# Sensor_v1_0.net
KiCad netlist of a schematic drawn in EAGLE
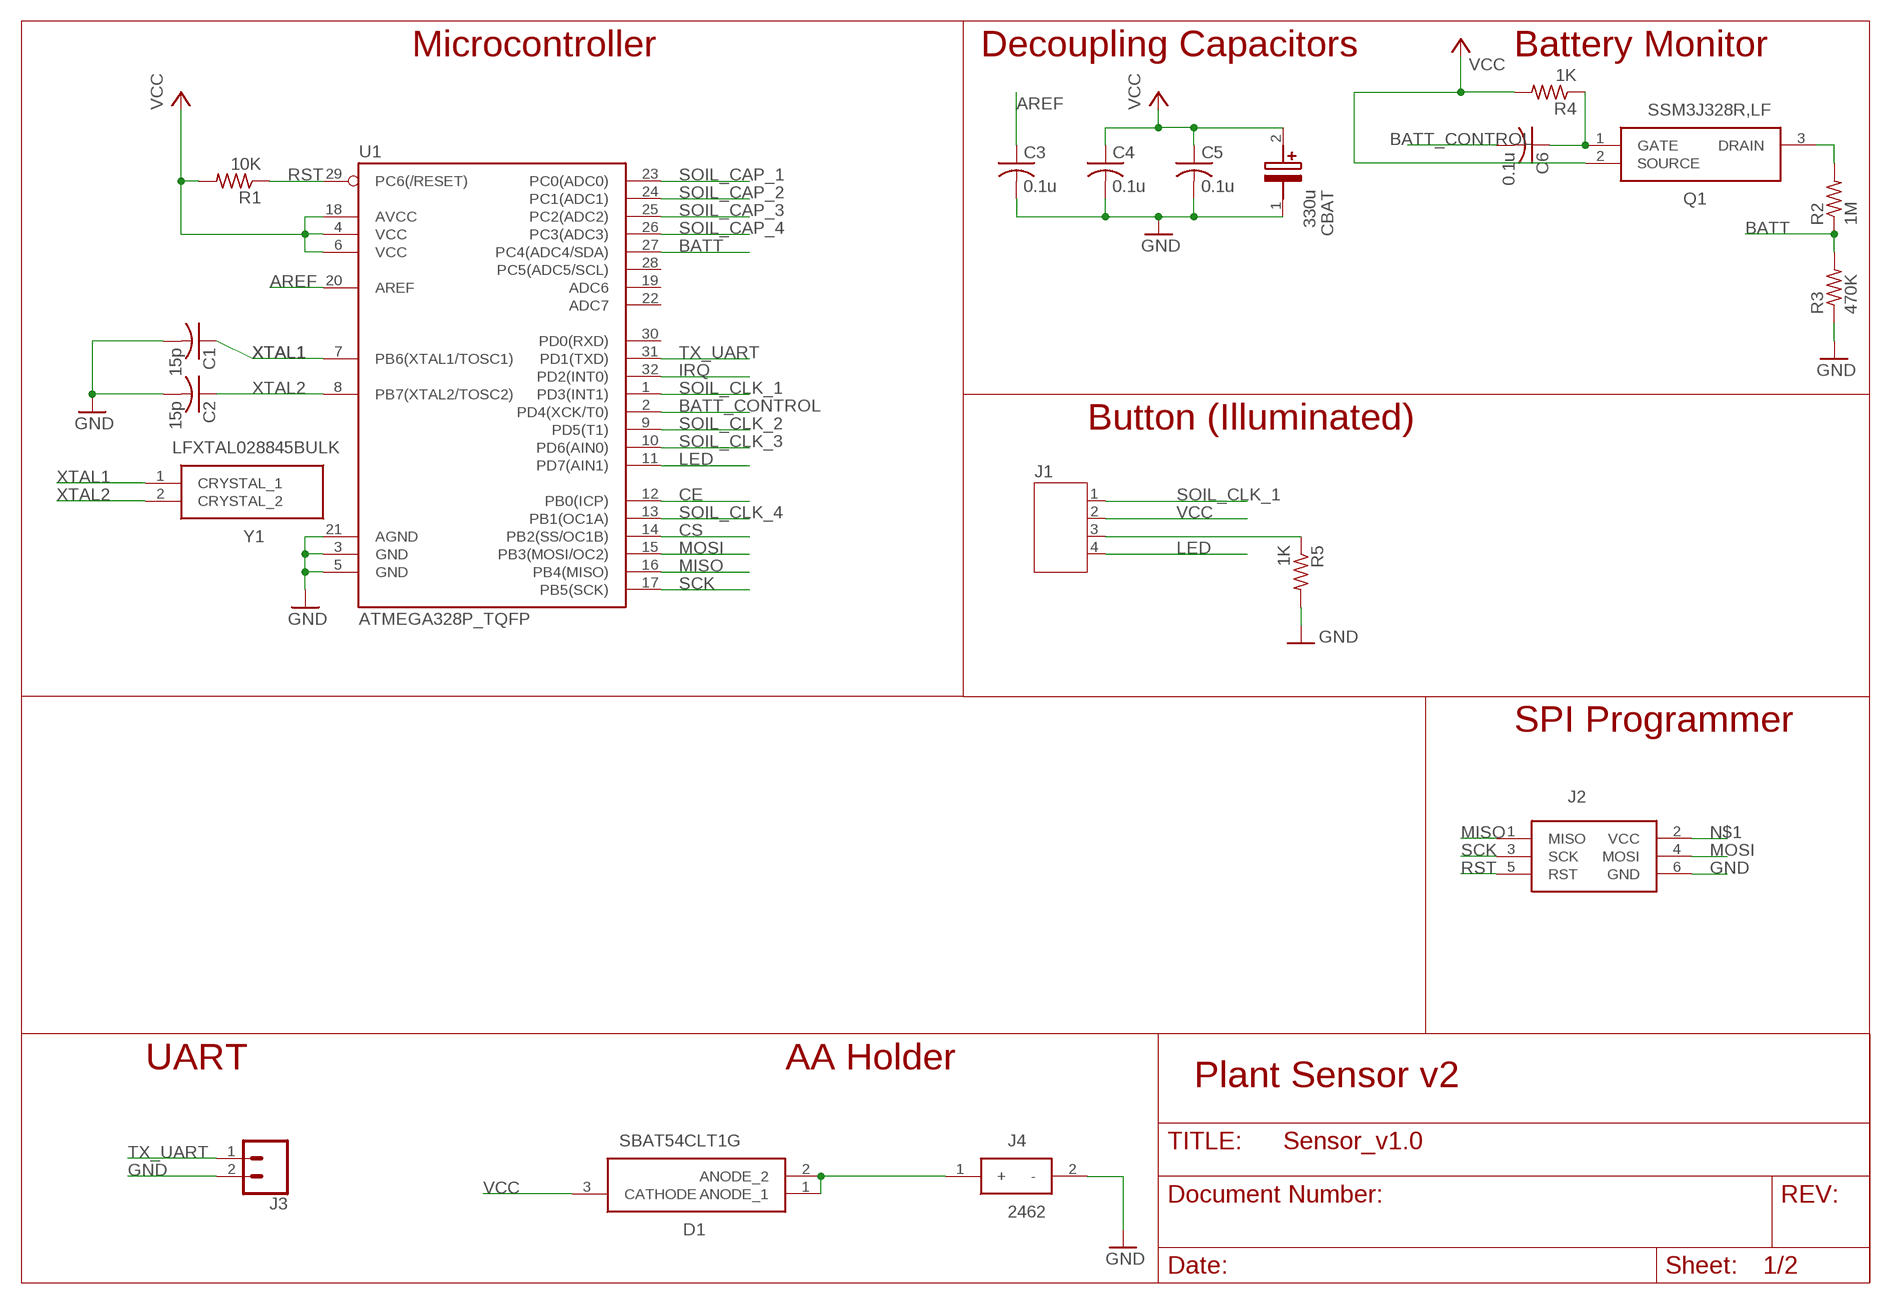
[diagram p0: schematic, sheet 1]
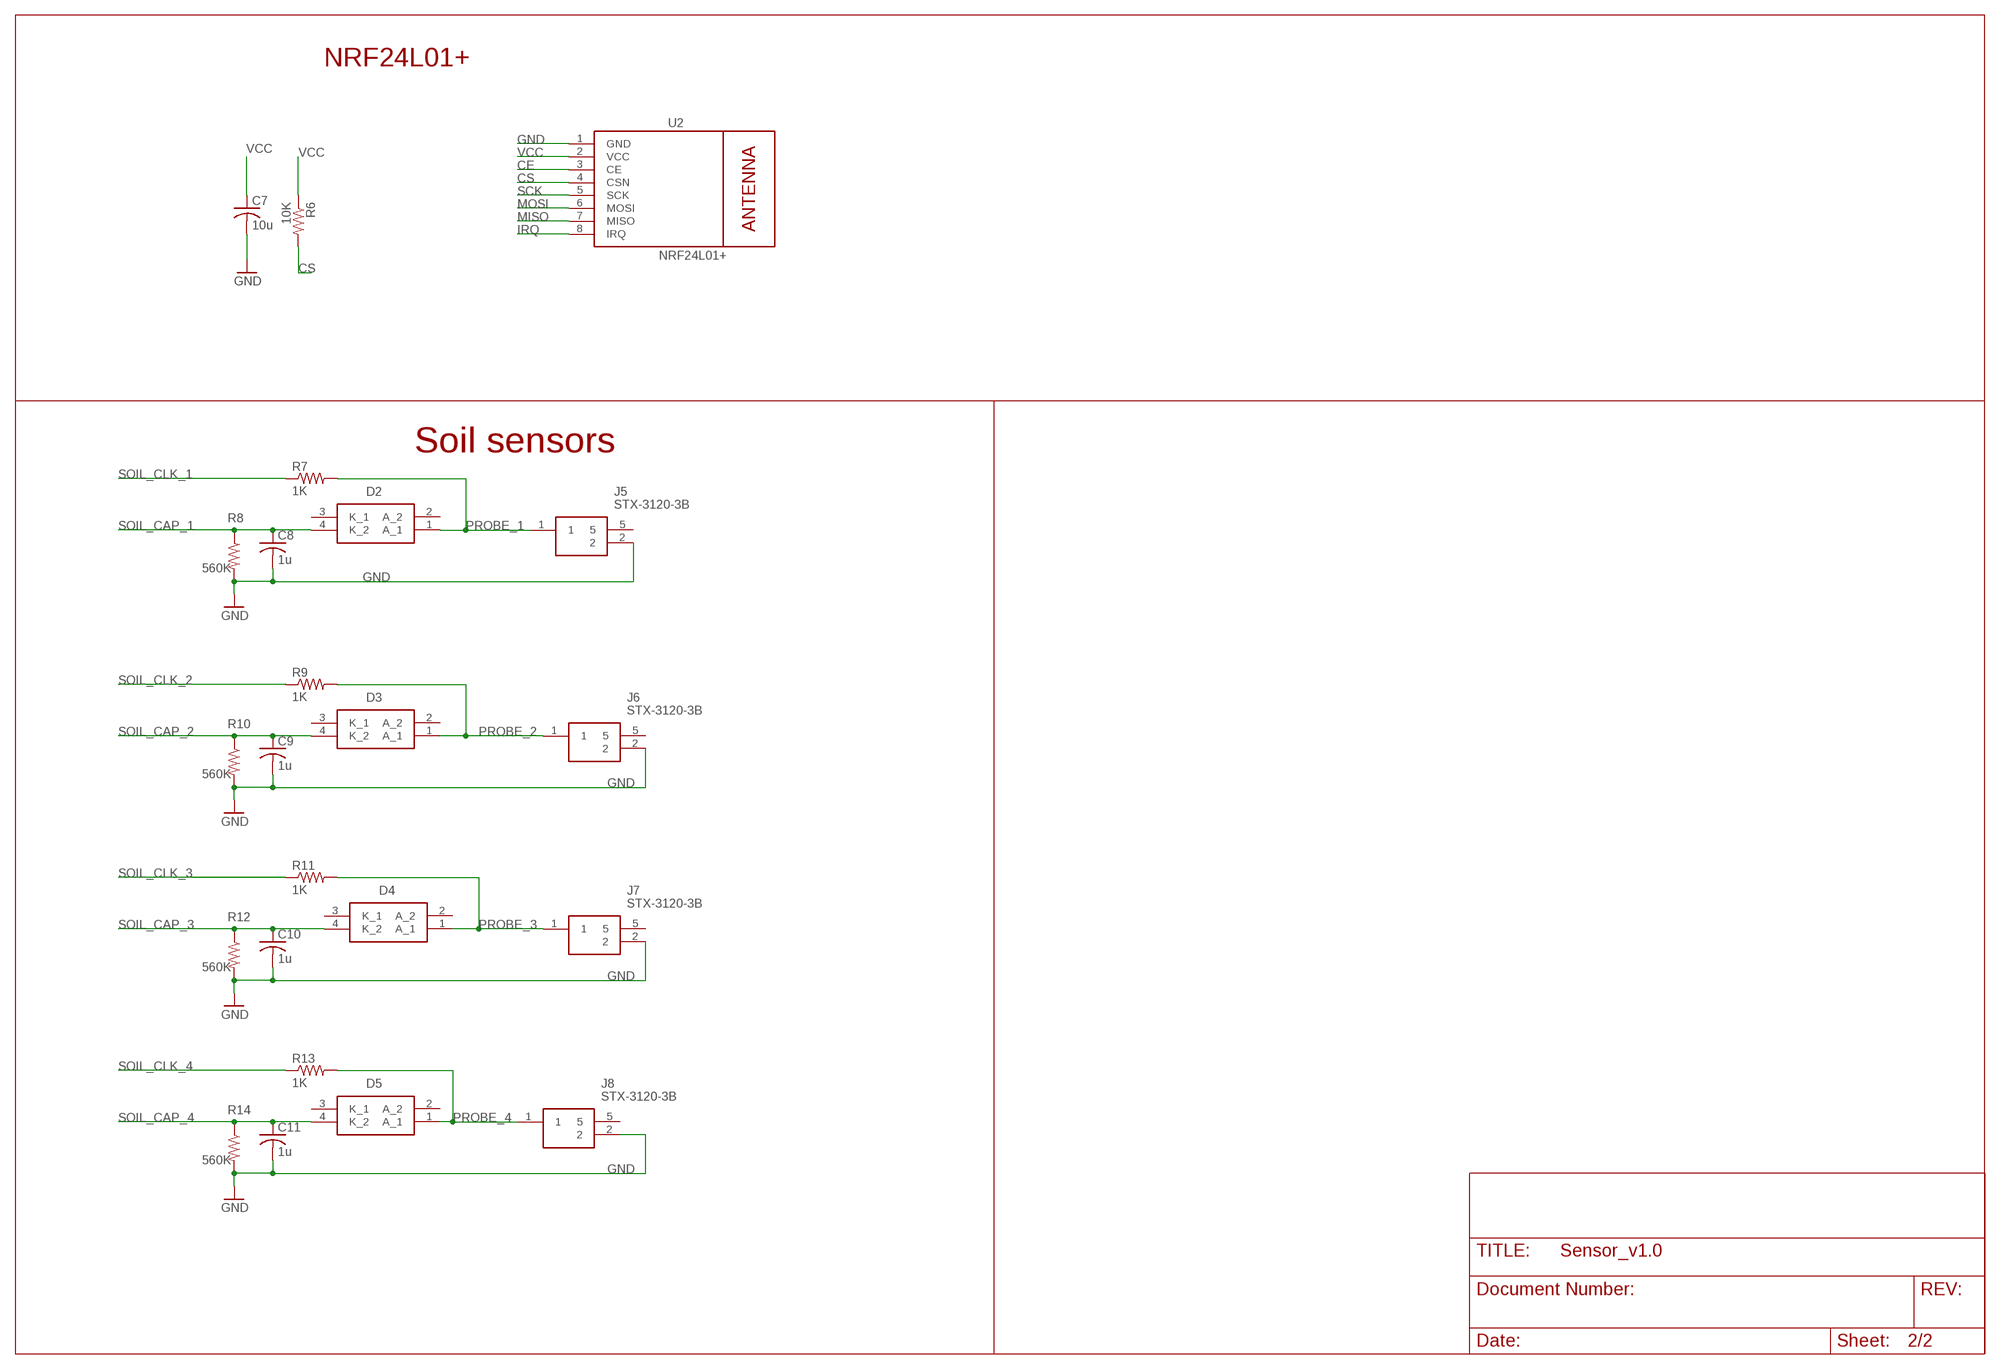
[diagram p1: schematic, sheet 2]

(export (version "E")
  (design (tool "Eeschema 10.0.6"))
  (components
    (comp (ref "C7")
      (value "10u")
      (footprint "eagle-import:SMD-0805")
      (libsource (lib "eagle-import") (part "CAPACITOR-SMD-0805"))
    )
    (comp (ref "C8")
      (value "1u")
      (footprint "eagle-import:SMD-0805")
      (libsource (lib "eagle-import") (part "CAPACITOR-SMD-0805"))
    )
    (comp (ref "C9")
      (value "1u")
      (footprint "eagle-import:SMD-0805")
      (libsource (lib "eagle-import") (part "CAPACITOR-SMD-0805"))
    )
    (comp (ref "C10")
      (value "1u")
      (footprint "eagle-import:SMD-0805")
      (libsource (lib "eagle-import") (part "CAPACITOR-SMD-0805"))
    )
    (comp (ref "C11")
      (value "1u")
      (footprint "eagle-import:SMD-0805")
      (libsource (lib "eagle-import") (part "CAPACITOR-SMD-0805"))
    )
    (comp (ref "D2")
      (value "1SS384TE85LF")
      (footprint "eagle-import:SOP65P210X110-4N")
      (fields (field (name "MOUSER_PART_NUMBER") "757-1SS384TE85LF"))
      (libsource (lib "eagle-import") (part "1SS384TE85LF"))
    )
    (comp (ref "D3")
      (value "1SS384TE85LF")
      (footprint "eagle-import:SOP65P210X110-4N")
      (fields (field (name "MOUSER_PART_NUMBER") "757-1SS384TE85LF"))
      (libsource (lib "eagle-import") (part "1SS384TE85LF"))
    )
    (comp (ref "D4")
      (value "1SS384TE85LF")
      (footprint "eagle-import:SOP65P210X110-4N")
      (fields (field (name "MOUSER_PART_NUMBER") "757-1SS384TE85LF"))
      (libsource (lib "eagle-import") (part "1SS384TE85LF"))
    )
    (comp (ref "D5")
      (value "1SS384TE85LF")
      (footprint "eagle-import:SOP65P210X110-4N")
      (fields (field (name "MOUSER_PART_NUMBER") "757-1SS384TE85LF"))
      (libsource (lib "eagle-import") (part "1SS384TE85LF"))
    )
    (comp (ref "J5")
      (value "STX-3120-3B")
      (footprint "eagle-import:STX31203B")
      (fields (field (name "MOUSER_PART_NUMBER") "806-STX-3120-3B"))
      (libsource (lib "eagle-import") (part "STX-3120-3B"))
    )
    (comp (ref "J6")
      (value "STX-3120-3B")
      (footprint "eagle-import:STX31203B")
      (fields (field (name "MOUSER_PART_NUMBER") "806-STX-3120-3B"))
      (libsource (lib "eagle-import") (part "STX-3120-3B"))
    )
    (comp (ref "J7")
      (value "STX-3120-3B")
      (footprint "eagle-import:STX31203B")
      (fields (field (name "MOUSER_PART_NUMBER") "806-STX-3120-3B"))
      (libsource (lib "eagle-import") (part "STX-3120-3B"))
    )
    (comp (ref "J8")
      (value "STX-3120-3B")
      (footprint "eagle-import:STX31203B")
      (fields (field (name "MOUSER_PART_NUMBER") "806-STX-3120-3B"))
      (libsource (lib "eagle-import") (part "STX-3120-3B"))
    )
    (comp (ref "R6")
      (value "10K")
      (footprint "eagle-import:SMD-0805")
      (libsource (lib "eagle-import") (part "RESISTOR-SMD-0805"))
    )
    (comp (ref "R7")
      (value "1K")
      (footprint "eagle-import:SMD-0805")
      (libsource (lib "eagle-import") (part "RESISTOR-SMD-0805"))
    )
    (comp (ref "R8")
      (value "560K")
      (footprint "eagle-import:SMD-0805")
      (libsource (lib "eagle-import") (part "RESISTOR-SMD-0805"))
    )
    (comp (ref "R9")
      (value "1K")
      (footprint "eagle-import:SMD-0805")
      (libsource (lib "eagle-import") (part "RESISTOR-SMD-0805"))
    )
    (comp (ref "R10")
      (value "560K")
      (footprint "eagle-import:SMD-0805")
      (libsource (lib "eagle-import") (part "RESISTOR-SMD-0805"))
    )
    (comp (ref "R11")
      (value "1K")
      (footprint "eagle-import:SMD-0805")
      (libsource (lib "eagle-import") (part "RESISTOR-SMD-0805"))
    )
    (comp (ref "R12")
      (value "560K")
      (footprint "eagle-import:SMD-0805")
      (libsource (lib "eagle-import") (part "RESISTOR-SMD-0805"))
    )
    (comp (ref "R13")
      (value "1K")
      (footprint "eagle-import:SMD-0805")
      (libsource (lib "eagle-import") (part "RESISTOR-SMD-0805"))
    )
    (comp (ref "R14")
      (value "560K")
      (footprint "eagle-import:SMD-0805")
      (libsource (lib "eagle-import") (part "RESISTOR-SMD-0805"))
    )
    (comp (ref "U2")
      (value "NRF24L01+")
      (footprint "eagle-import:WIRELESS-NRF24L01")
      (libsource (lib "eagle-import") (part "WIRELESS-NRF24L01"))
    )
    (comp (ref "C1")
      (value "15p")
      (footprint "eagle-import:SMD-0805")
      (libsource (lib "eagle-import") (part "CAPACITOR-SMD-0805"))
    )
    (comp (ref "C2")
      (value "15p")
      (footprint "eagle-import:SMD-0805")
      (libsource (lib "eagle-import") (part "CAPACITOR-SMD-0805"))
    )
    (comp (ref "C3")
      (value "0.1u")
      (footprint "eagle-import:SMD-0805")
      (libsource (lib "eagle-import") (part "CAPACITOR-SMD-0805"))
    )
    (comp (ref "C4")
      (value "0.1u")
      (footprint "eagle-import:SMD-0805")
      (libsource (lib "eagle-import") (part "CAPACITOR-SMD-0805"))
    )
    (comp (ref "C5")
      (value "0.1u")
      (footprint "eagle-import:SMD-0805")
      (libsource (lib "eagle-import") (part "CAPACITOR-SMD-0805"))
    )
    (comp (ref "C6")
      (value "0.1u")
      (footprint "eagle-import:SMD-0805")
      (libsource (lib "eagle-import") (part "CAPACITOR-SMD-0805"))
    )
    (comp (ref "CBAT")
      (value "330u")
      (footprint "eagle-import:SMD_LYTIC_D8")
      (fields
        (field (name "MANUFACTURER_PART_NUMBER") "EEE-FNC271XUP")
        (field (name "MOUSER_PART_NUMBER") "667-EEE-FNC271XUP")
      )
      (libsource (lib "eagle-import") (part "EEE-FNC271XUP"))
    )
    (comp (ref "D1")
      (value "SBAT54CLT1G")
      (footprint "eagle-import:SOT96P237X111-3N")
      (fields (field (name "MOUSER_PART_NUMBER") "863-SBAT54CLT1G"))
      (libsource (lib "eagle-import") (part "SBAT54CLT1G"))
    )
    (comp (ref "J1")
      (value "JST-PH4")
      (footprint "eagle-import:JST-PH4")
      (libsource (lib "eagle-import") (part "JST-PH4"))
    )
    (comp (ref "J2")
      (value "ISP")
      (footprint "eagle-import:AVRISP")
      (libsource (lib "eagle-import") (part "AVRISP-6"))
    )
    (comp (ref "J3")
      (value "CONN_02")
      (footprint "eagle-import:1X02")
      (libsource (lib "eagle-import") (part "CONN_02"))
    )
    (comp (ref "J4")
      (value "2462")
      (footprint "eagle-import:2462")
      (fields (field (name "MOUSER_PART_NUMBER") "534-2462"))
      (libsource (lib "eagle-import") (part "2462"))
    )
    (comp (ref "Q1")
      (value "SSM3J328R,LF")
      (footprint "eagle-import:SOTFL95P240X88-3N")
      (fields (field (name "MOUSER_PART_NUMBER") "757-SSM3J328RLF"))
      (libsource (lib "eagle-import") (part "SSM3J328R,LF"))
    )
    (comp (ref "R1")
      (value "10K")
      (footprint "eagle-import:SMD-0805")
      (libsource (lib "eagle-import") (part "RESISTOR-SMD-0805"))
    )
    (comp (ref "R2")
      (value "1M")
      (footprint "eagle-import:SMD-0805")
      (libsource (lib "eagle-import") (part "RESISTOR-SMD-0805"))
    )
    (comp (ref "R3")
      (value "470K")
      (footprint "eagle-import:SMD-0805")
      (libsource (lib "eagle-import") (part "RESISTOR-SMD-0805"))
    )
    (comp (ref "R4")
      (value "1K")
      (footprint "eagle-import:SMD-0805")
      (libsource (lib "eagle-import") (part "RESISTOR-SMD-0805"))
    )
    (comp (ref "R5")
      (value "1K")
      (footprint "eagle-import:SMD-0805")
      (libsource (lib "eagle-import") (part "RESISTOR-SMD-0805"))
    )
    (comp (ref "U1")
      (value "ATMEGA328P_TQFP")
      (footprint "eagle-import:TQFP32-08")
      (libsource (lib "eagle-import") (part "ATMEGA328P_TQFP"))
    )
    (comp (ref "Y1")
      (value "LFXTAL028845BULK")
      (footprint "eagle-import:LFXTAL028845BULK")
      (libsource (lib "eagle-import") (part "LFXTAL028845BULK"))
    )
  )
  (nets
    (net (code "1") (name "AREF") (class "Default")
      (node (ref "C3") (pin "1") (pinfunction "1_1") (pintype "passive"))
      (node (ref "U1") (pin "20") (pinfunction "AREF_20") (pintype "bidirectional"))
    )
    (net (code "2") (name "BATT") (class "Default")
      (node (ref "R2") (pin "1") (pinfunction "1_1") (pintype "passive"))
      (node (ref "R3") (pin "2") (pinfunction "2_2") (pintype "passive"))
      (node (ref "U1") (pin "27") (pinfunction "PC4(ADC4/SDA)_27") (pintype "bidirectional"))
    )
    (net (code "3") (name "BATT_CONTROL") (class "Default")
      (node (ref "C6") (pin "2") (pinfunction "2_2") (pintype "passive"))
      (node (ref "U1") (pin "2") (pinfunction "PD4(XCK/T0)_2") (pintype "bidirectional"))
    )
    (net (code "4") (name "CE") (class "Default")
      (node (ref "U1") (pin "12") (pinfunction "PB0(ICP)_12") (pintype "bidirectional"))
      (node (ref "U2") (pin "3") (pinfunction "CE_3") (pintype "bidirectional"))
    )
    (net (code "5") (name "CS") (class "Default")
      (node (ref "R6") (pin "2") (pinfunction "2_2") (pintype "passive"))
      (node (ref "U1") (pin "14") (pinfunction "PB2(SS/OC1B)_14") (pintype "bidirectional"))
      (node (ref "U2") (pin "4") (pinfunction "CSN_4") (pintype "bidirectional"))
    )
    (net (code "6") (name "GND") (class "Default")
      (node (ref "C1") (pin "2") (pinfunction "2_2") (pintype "passive"))
      (node (ref "C10") (pin "2") (pinfunction "2_2") (pintype "passive"))
      (node (ref "C11") (pin "2") (pinfunction "2_2") (pintype "passive"))
      (node (ref "C2") (pin "2") (pinfunction "2_2") (pintype "passive"))
      (node (ref "C3") (pin "2") (pinfunction "2_2") (pintype "passive"))
      (node (ref "C4") (pin "2") (pinfunction "2_2") (pintype "passive"))
      (node (ref "C5") (pin "2") (pinfunction "2_2") (pintype "passive"))
      (node (ref "C7") (pin "2") (pinfunction "2_2") (pintype "passive"))
      (node (ref "C8") (pin "2") (pinfunction "2_2") (pintype "passive"))
      (node (ref "C9") (pin "2") (pinfunction "2_2") (pintype "passive"))
      (node (ref "CBAT") (pin "1") (pinfunction "1_1") (pintype "bidirectional"))
      (node (ref "J2") (pin "6") (pinfunction "GND_6") (pintype "power_in"))
      (node (ref "J3") (pin "2") (pinfunction "2_2") (pintype "passive"))
      (node (ref "J4") (pin "2") (pinfunction "-_2") (pintype "bidirectional"))
      (node (ref "J5") (pin "2") (pinfunction "2_2") (pintype "bidirectional"))
      (node (ref "J6") (pin "2") (pinfunction "2_2") (pintype "bidirectional"))
      (node (ref "J7") (pin "2") (pinfunction "2_2") (pintype "bidirectional"))
      (node (ref "J8") (pin "2") (pinfunction "2_2") (pintype "bidirectional"))
      (node (ref "R10") (pin "2") (pinfunction "2_2") (pintype "passive"))
      (node (ref "R12") (pin "2") (pinfunction "2_2") (pintype "passive"))
      (node (ref "R14") (pin "2") (pinfunction "2_2") (pintype "passive"))
      (node (ref "R3") (pin "1") (pinfunction "1_1") (pintype "passive"))
      (node (ref "R5") (pin "2") (pinfunction "2_2") (pintype "passive"))
      (node (ref "R8") (pin "2") (pinfunction "2_2") (pintype "passive"))
      (node (ref "U1") (pin "21") (pinfunction "AGND_21") (pintype "bidirectional"))
      (node (ref "U1") (pin "3") (pinfunction "GND_3") (pintype "bidirectional"))
      (node (ref "U1") (pin "5") (pinfunction "GND_5") (pintype "bidirectional"))
      (node (ref "U2") (pin "1") (pinfunction "GND_1") (pintype "power_in"))
    )
    (net (code "7") (name "IRQ") (class "Default")
      (node (ref "U1") (pin "32") (pinfunction "PD2(INT0)_32") (pintype "bidirectional"))
      (node (ref "U2") (pin "8") (pinfunction "IRQ_8") (pintype "bidirectional"))
    )
    (net (code "8") (name "LED") (class "Default")
      (node (ref "J1") (pin "4") (pinfunction "4_4") (pintype "passive"))
      (node (ref "U1") (pin "11") (pinfunction "PD7(AIN1)_11") (pintype "bidirectional"))
    )
    (net (code "9") (name "MISO") (class "Default")
      (node (ref "J2") (pin "1") (pinfunction "MISO_1") (pintype "input"))
      (node (ref "U1") (pin "16") (pinfunction "PB4(MISO)_16") (pintype "bidirectional"))
      (node (ref "U2") (pin "7") (pinfunction "MISO_7") (pintype "bidirectional"))
    )
    (net (code "10") (name "MOSI") (class "Default")
      (node (ref "J2") (pin "4") (pinfunction "MOSI_4") (pintype "output"))
      (node (ref "U1") (pin "15") (pinfunction "PB3(MOSI/OC2)_15") (pintype "bidirectional"))
      (node (ref "U2") (pin "6") (pinfunction "MOSI_6") (pintype "bidirectional"))
    )
    (net (code "11") (name "N$1") (class "Default")
      (node (ref "J2") (pin "2") (pinfunction "VCC_2") (pintype "power_in"))
    )
    (net (code "12") (name "Net-(D1-ANODE_1)") (class "Default")
      (node (ref "D1") (pin "1") (pinfunction "ANODE_1_1") (pintype "bidirectional"))
      (node (ref "D1") (pin "2") (pinfunction "ANODE_2_2") (pintype "bidirectional"))
      (node (ref "J4") (pin "1") (pinfunction "+_1") (pintype "bidirectional"))
    )
    (net (code "13") (name "Net-(J1-Pad3)") (class "Default")
      (node (ref "J1") (pin "3") (pinfunction "3_3") (pintype "passive"))
      (node (ref "R5") (pin "1") (pinfunction "1_1") (pintype "passive"))
    )
    (net (code "14") (name "Net-(Q1-DRAIN)") (class "Default")
      (node (ref "Q1") (pin "3") (pinfunction "DRAIN_3") (pintype "bidirectional"))
      (node (ref "R2") (pin "2") (pinfunction "2_2") (pintype "passive"))
    )
    (net (code "15") (name "Net-(Q1-GATE)") (class "Default")
      (node (ref "C6") (pin "1") (pinfunction "1_1") (pintype "passive"))
      (node (ref "Q1") (pin "1") (pinfunction "GATE_1") (pintype "input"))
      (node (ref "R4") (pin "1") (pinfunction "1_1") (pintype "passive"))
    )
    (net (code "16") (name "PROBE_1") (class "Default")
      (node (ref "D2") (pin "1") (pinfunction "A_1_1") (pintype "bidirectional"))
      (node (ref "J5") (pin "1") (pinfunction "1_1") (pintype "bidirectional"))
      (node (ref "R7") (pin "2") (pinfunction "2_2") (pintype "passive"))
    )
    (net (code "17") (name "PROBE_2") (class "Default")
      (node (ref "D3") (pin "1") (pinfunction "A_1_1") (pintype "bidirectional"))
      (node (ref "J6") (pin "1") (pinfunction "1_1") (pintype "bidirectional"))
      (node (ref "R9") (pin "2") (pinfunction "2_2") (pintype "passive"))
    )
    (net (code "18") (name "PROBE_3") (class "Default")
      (node (ref "D4") (pin "1") (pinfunction "A_1_1") (pintype "bidirectional"))
      (node (ref "J7") (pin "1") (pinfunction "1_1") (pintype "bidirectional"))
      (node (ref "R11") (pin "2") (pinfunction "2_2") (pintype "passive"))
    )
    (net (code "19") (name "PROBE_4") (class "Default")
      (node (ref "D5") (pin "1") (pinfunction "A_1_1") (pintype "bidirectional"))
      (node (ref "J8") (pin "1") (pinfunction "1_1") (pintype "bidirectional"))
      (node (ref "R13") (pin "2") (pinfunction "2_2") (pintype "passive"))
    )
    (net (code "20") (name "RST") (class "Default")
      (node (ref "J2") (pin "5") (pinfunction "RST_5") (pintype "output"))
      (node (ref "R1") (pin "1") (pinfunction "1_1") (pintype "passive"))
      (node (ref "U1") (pin "29") (pinfunction "PC6(/RESET)_29") (pintype "bidirectional"))
    )
    (net (code "21") (name "SCK") (class "Default")
      (node (ref "J2") (pin "3") (pinfunction "SCK_3") (pintype "output"))
      (node (ref "U1") (pin "17") (pinfunction "PB5(SCK)_17") (pintype "bidirectional"))
      (node (ref "U2") (pin "5") (pinfunction "SCK_5") (pintype "bidirectional"))
    )
    (net (code "22") (name "SOIL_CAP_1") (class "Default")
      (node (ref "C8") (pin "1") (pinfunction "1_1") (pintype "passive"))
      (node (ref "D2") (pin "4") (pinfunction "K_2_4") (pintype "bidirectional"))
      (node (ref "R8") (pin "1") (pinfunction "1_1") (pintype "passive"))
      (node (ref "U1") (pin "23") (pinfunction "PC0(ADC0)_23") (pintype "bidirectional"))
    )
    (net (code "23") (name "SOIL_CAP_2") (class "Default")
      (node (ref "C9") (pin "1") (pinfunction "1_1") (pintype "passive"))
      (node (ref "D3") (pin "4") (pinfunction "K_2_4") (pintype "bidirectional"))
      (node (ref "R10") (pin "1") (pinfunction "1_1") (pintype "passive"))
      (node (ref "U1") (pin "24") (pinfunction "PC1(ADC1)_24") (pintype "bidirectional"))
    )
    (net (code "24") (name "SOIL_CAP_3") (class "Default")
      (node (ref "C10") (pin "1") (pinfunction "1_1") (pintype "passive"))
      (node (ref "D4") (pin "4") (pinfunction "K_2_4") (pintype "bidirectional"))
      (node (ref "R12") (pin "1") (pinfunction "1_1") (pintype "passive"))
      (node (ref "U1") (pin "25") (pinfunction "PC2(ADC2)_25") (pintype "bidirectional"))
    )
    (net (code "25") (name "SOIL_CAP_4") (class "Default")
      (node (ref "C11") (pin "1") (pinfunction "1_1") (pintype "passive"))
      (node (ref "D5") (pin "4") (pinfunction "K_2_4") (pintype "bidirectional"))
      (node (ref "R14") (pin "1") (pinfunction "1_1") (pintype "passive"))
      (node (ref "U1") (pin "26") (pinfunction "PC3(ADC3)_26") (pintype "bidirectional"))
    )
    (net (code "26") (name "SOIL_CLK_1") (class "Default")
      (node (ref "J1") (pin "1") (pinfunction "1_1") (pintype "passive"))
      (node (ref "R7") (pin "1") (pinfunction "1_1") (pintype "passive"))
      (node (ref "U1") (pin "1") (pinfunction "PD3(INT1)_1") (pintype "bidirectional"))
    )
    (net (code "27") (name "SOIL_CLK_2") (class "Default")
      (node (ref "R9") (pin "1") (pinfunction "1_1") (pintype "passive"))
      (node (ref "U1") (pin "9") (pinfunction "PD5(T1)_9") (pintype "bidirectional"))
    )
    (net (code "28") (name "SOIL_CLK_3") (class "Default")
      (node (ref "R11") (pin "1") (pinfunction "1_1") (pintype "passive"))
      (node (ref "U1") (pin "10") (pinfunction "PD6(AIN0)_10") (pintype "bidirectional"))
    )
    (net (code "29") (name "SOIL_CLK_4") (class "Default")
      (node (ref "R13") (pin "1") (pinfunction "1_1") (pintype "passive"))
      (node (ref "U1") (pin "13") (pinfunction "PB1(OC1A)_13") (pintype "bidirectional"))
    )
    (net (code "30") (name "TX_UART") (class "Default")
      (node (ref "J3") (pin "1") (pinfunction "1_1") (pintype "passive"))
      (node (ref "U1") (pin "31") (pinfunction "PD1(TXD)_31") (pintype "bidirectional"))
    )
    (net (code "31") (name "VCC") (class "Default")
      (node (ref "C4") (pin "1") (pinfunction "1_1") (pintype "passive"))
      (node (ref "C5") (pin "1") (pinfunction "1_1") (pintype "passive"))
      (node (ref "C7") (pin "1") (pinfunction "1_1") (pintype "passive"))
      (node (ref "CBAT") (pin "2") (pinfunction "2_2") (pintype "bidirectional"))
      (node (ref "D1") (pin "3") (pinfunction "CATHODE_3") (pintype "bidirectional"))
      (node (ref "J1") (pin "2") (pinfunction "2_2") (pintype "passive"))
      (node (ref "Q1") (pin "2") (pinfunction "SOURCE_2") (pintype "bidirectional"))
      (node (ref "R1") (pin "2") (pinfunction "2_2") (pintype "passive"))
      (node (ref "R4") (pin "2") (pinfunction "2_2") (pintype "passive"))
      (node (ref "R6") (pin "1") (pinfunction "1_1") (pintype "passive"))
      (node (ref "U1") (pin "18") (pinfunction "AVCC_18") (pintype "bidirectional"))
      (node (ref "U1") (pin "4") (pinfunction "VCC_4") (pintype "bidirectional"))
      (node (ref "U1") (pin "6") (pinfunction "VCC_6") (pintype "bidirectional"))
      (node (ref "U2") (pin "2") (pinfunction "VCC_2") (pintype "power_in"))
    )
    (net (code "32") (name "XTAL1") (class "Default")
      (node (ref "C1") (pin "1") (pinfunction "1_1") (pintype "passive"))
      (node (ref "U1") (pin "7") (pinfunction "PB6(XTAL1/TOSC1)_7") (pintype "bidirectional"))
      (node (ref "Y1") (pin "1") (pinfunction "CRYSTAL_1_1") (pintype "bidirectional"))
    )
    (net (code "33") (name "XTAL2") (class "Default")
      (node (ref "C2") (pin "1") (pinfunction "1_1") (pintype "passive"))
      (node (ref "U1") (pin "8") (pinfunction "PB7(XTAL2/TOSC2)_8") (pintype "bidirectional"))
      (node (ref "Y1") (pin "2") (pinfunction "CRYSTAL_2_2") (pintype "bidirectional"))
    )
    (net (code "34") (name "unconnected-(D2-A_2-Pad2)") (class "Default")
      (node (ref "D2") (pin "2") (pinfunction "A_2_2") (pintype "bidirectional"))
    )
    (net (code "35") (name "unconnected-(D2-K_1-Pad3)") (class "Default")
      (node (ref "D2") (pin "3") (pinfunction "K_1_3") (pintype "bidirectional"))
    )
    (net (code "36") (name "unconnected-(D3-A_2-Pad2)") (class "Default")
      (node (ref "D3") (pin "2") (pinfunction "A_2_2") (pintype "bidirectional"))
    )
    (net (code "37") (name "unconnected-(D3-K_1-Pad3)") (class "Default")
      (node (ref "D3") (pin "3") (pinfunction "K_1_3") (pintype "bidirectional"))
    )
    (net (code "38") (name "unconnected-(D4-A_2-Pad2)") (class "Default")
      (node (ref "D4") (pin "2") (pinfunction "A_2_2") (pintype "bidirectional"))
    )
    (net (code "39") (name "unconnected-(D4-K_1-Pad3)") (class "Default")
      (node (ref "D4") (pin "3") (pinfunction "K_1_3") (pintype "bidirectional"))
    )
    (net (code "40") (name "unconnected-(D5-A_2-Pad2)") (class "Default")
      (node (ref "D5") (pin "2") (pinfunction "A_2_2") (pintype "bidirectional"))
    )
    (net (code "41") (name "unconnected-(D5-K_1-Pad3)") (class "Default")
      (node (ref "D5") (pin "3") (pinfunction "K_1_3") (pintype "bidirectional"))
    )
    (net (code "42") (name "unconnected-(J5-Pad5)") (class "Default")
      (node (ref "J5") (pin "5") (pinfunction "5_5") (pintype "bidirectional"))
    )
    (net (code "43") (name "unconnected-(J6-Pad5)") (class "Default")
      (node (ref "J6") (pin "5") (pinfunction "5_5") (pintype "bidirectional"))
    )
    (net (code "44") (name "unconnected-(J7-Pad5)") (class "Default")
      (node (ref "J7") (pin "5") (pinfunction "5_5") (pintype "bidirectional"))
    )
    (net (code "45") (name "unconnected-(J8-Pad5)") (class "Default")
      (node (ref "J8") (pin "5") (pinfunction "5_5") (pintype "bidirectional"))
    )
    (net (code "46") (name "unconnected-(U1-ADC6-Pad19)") (class "Default")
      (node (ref "U1") (pin "19") (pinfunction "ADC6_19") (pintype "bidirectional"))
    )
    (net (code "47") (name "unconnected-(U1-ADC7-Pad22)") (class "Default")
      (node (ref "U1") (pin "22") (pinfunction "ADC7_22") (pintype "bidirectional"))
    )
    (net (code "48") (name "unconnected-(U1-PC5(ADC5{slash}SCL)-Pad28)") (class "Default")
      (node (ref "U1") (pin "28") (pinfunction "PC5(ADC5/SCL)_28") (pintype "bidirectional"))
    )
    (net (code "49") (name "unconnected-(U1-PD0(RXD)-Pad30)") (class "Default")
      (node (ref "U1") (pin "30") (pinfunction "PD0(RXD)_30") (pintype "bidirectional"))
    )
  )
)
